# stepper.net
KiCad netlist of a schematic drawn in EAGLE
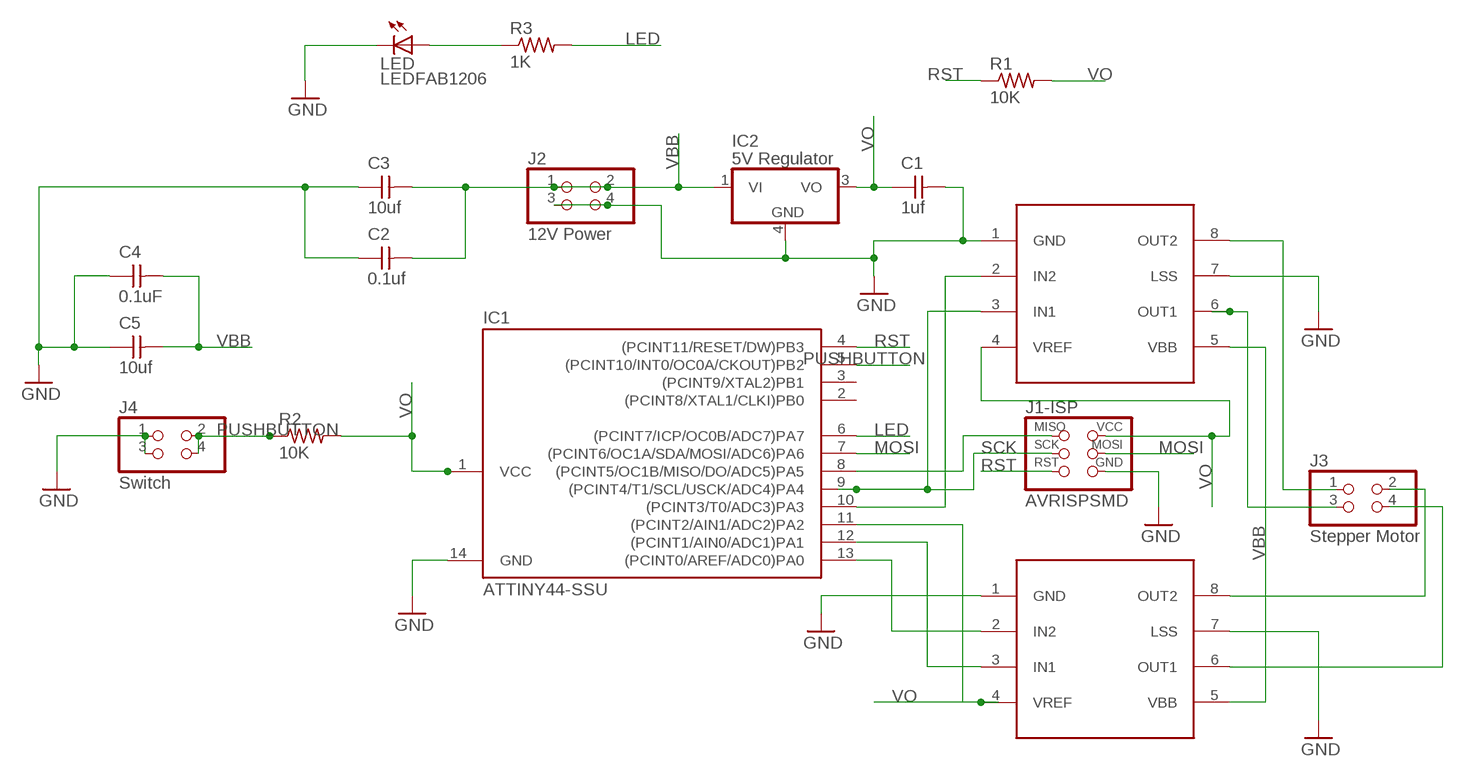
[diagram p0: schematic, sheet 1]

(export (version "E")
  (design (tool "Eeschema 10.0.6"))
  (components
    (comp (ref "C1")
      (value "1uf")
      (footprint "eagle-import:C1206FAB")
      (libsource (lib "eagle-import") (part "CAP-UNPOLARIZEDFAB"))
    )
    (comp (ref "C2")
      (value "0.1uf")
      (footprint "eagle-import:C1206FAB")
      (libsource (lib "eagle-import") (part "CAP-UNPOLARIZEDFAB"))
    )
    (comp (ref "C3")
      (value "10uf")
      (footprint "eagle-import:C1206FAB")
      (libsource (lib "eagle-import") (part "CAP-UNPOLARIZEDFAB"))
    )
    (comp (ref "C4")
      (value "0.1uF")
      (footprint "eagle-import:C1206FAB")
      (libsource (lib "eagle-import") (part "CAP-UNPOLARIZEDFAB"))
    )
    (comp (ref "C5")
      (value "10uf")
      (footprint "eagle-import:C1206FAB")
      (libsource (lib "eagle-import") (part "CAP-UNPOLARIZEDFAB"))
    )
    (comp (ref "IC1")
      (value "ATTINY44-SSU")
      (footprint "eagle-import:SOIC14")
      (libsource (lib "eagle-import") (part "ATTINY44-SSU"))
    )
    (comp (ref "IC2")
      (value "5V Regulator")
      (footprint "eagle-import:SOT223")
      (libsource (lib "eagle-import") (part "LM340?-MP05"))
    )
    (comp (ref "IC3")
      (value "A4950")
      (footprint "eagle-import:SOIC8")
      (libsource (lib "eagle-import") (part "A4953-H-BRIDGE-MOTOR-DRIVER"))
    )
    (comp (ref "IC4")
      (value "A4950")
      (footprint "eagle-import:SOIC8")
      (libsource (lib "eagle-import") (part "A4953-H-BRIDGE-MOTOR-DRIVER"))
    )
    (comp (ref "J1-ISP")
      (value "AVRISPSMD")
      (footprint "eagle-import:2X03SMD")
      (libsource (lib "eagle-import") (part "AVRISPSMD"))
    )
    (comp (ref "J2")
      (value "12V Power")
      (footprint "eagle-import:2X02SMD")
      (libsource (lib "eagle-import") (part "PINHD-2X2-SMD"))
    )
    (comp (ref "J3")
      (value "Stepper Motor")
      (footprint "eagle-import:2X02SMD")
      (libsource (lib "eagle-import") (part "PINHD-2X2-SMD"))
    )
    (comp (ref "J4")
      (value "Switch")
      (footprint "eagle-import:2X02SMD")
      (libsource (lib "eagle-import") (part "PINHD-2X2-SMD"))
    )
    (comp (ref "LED")
      (value "LEDFAB1206")
      (footprint "eagle-import:LED1206FAB")
      (libsource (lib "eagle-import") (part "LEDFAB1206"))
    )
    (comp (ref "R1")
      (value "10K")
      (footprint "eagle-import:R1206FAB")
      (libsource (lib "eagle-import") (part "RES-US1206FAB"))
    )
    (comp (ref "R2")
      (value "10K")
      (footprint "eagle-import:R1206FAB")
      (libsource (lib "eagle-import") (part "RES-US1206FAB"))
    )
    (comp (ref "R3")
      (value "1K")
      (footprint "eagle-import:R1206FAB")
      (libsource (lib "eagle-import") (part "RES-US1206FAB"))
    )
  )
  (nets
    (net (code "1") (name "/LED") (class "Default")
      (node (ref "IC1") (pin "6") (pinfunction "(PCINT7/ICP/OC0B/ADC7)PA7_6") (pintype "bidirectional"))
      (node (ref "R3") (pin "2") (pinfunction "2_2") (pintype "passive"))
    )
    (net (code "2") (name "/MOSI") (class "Default")
      (node (ref "IC1") (pin "7") (pinfunction "(PCINT6/OC1A/SDA/MOSI/ADC6)PA6_7") (pintype "bidirectional"))
      (node (ref "J1-ISP") (pin "4") (pinfunction "MOSI_4") (pintype "passive"))
    )
    (net (code "3") (name "/PUSHBUTTON") (class "Default")
      (node (ref "IC1") (pin "5") (pinfunction "(PCINT10/INT0/OC0A/CKOUT)PB2_5") (pintype "bidirectional"))
      (node (ref "J4") (pin "2") (pinfunction "2_2") (pintype "passive"))
      (node (ref "J4") (pin "4") (pinfunction "4_4") (pintype "passive"))
      (node (ref "R2") (pin "1") (pinfunction "1_1") (pintype "passive"))
    )
    (net (code "4") (name "/RST") (class "Default")
      (node (ref "IC1") (pin "4") (pinfunction "(PCINT11/RESET/DW)PB3_4") (pintype "bidirectional"))
      (node (ref "J1-ISP") (pin "5") (pinfunction "RST_5") (pintype "passive"))
      (node (ref "R1") (pin "1") (pinfunction "1_1") (pintype "passive"))
    )
    (net (code "5") (name "/SCK") (class "Default")
      (node (ref "IC1") (pin "9") (pinfunction "(PCINT4/T1/SCL/USCK/ADC4)PA4_9") (pintype "bidirectional"))
      (node (ref "IC4") (pin "3") (pinfunction "IN1_3") (pintype "bidirectional"))
      (node (ref "J1-ISP") (pin "3") (pinfunction "SCK_3") (pintype "passive"))
    )
    (net (code "6") (name "/VBB") (class "Default")
      (node (ref "C2") (pin "2") (pinfunction "2_2") (pintype "passive"))
      (node (ref "C3") (pin "2") (pinfunction "2_2") (pintype "passive"))
      (node (ref "C4") (pin "2") (pinfunction "2_2") (pintype "passive"))
      (node (ref "C5") (pin "2") (pinfunction "2_2") (pintype "passive"))
      (node (ref "IC2") (pin "1") (pinfunction "VI_1") (pintype "input"))
      (node (ref "IC3") (pin "5") (pinfunction "VBB_5") (pintype "bidirectional"))
      (node (ref "IC4") (pin "5") (pinfunction "VBB_5") (pintype "bidirectional"))
      (node (ref "J2") (pin "1") (pinfunction "1_1") (pintype "passive"))
      (node (ref "J2") (pin "2") (pinfunction "2_2") (pintype "passive"))
    )
    (net (code "7") (name "/VO") (class "Default")
      (node (ref "C1") (pin "1") (pinfunction "1_1") (pintype "passive"))
      (node (ref "IC1") (pin "1") (pinfunction "VCC_1") (pintype "power_in"))
      (node (ref "IC1") (pin "11") (pinfunction "(PCINT2/AIN1/ADC2)PA2_11") (pintype "bidirectional"))
      (node (ref "IC2") (pin "3") (pinfunction "VO_3") (pintype "passive"))
      (node (ref "IC3") (pin "4") (pinfunction "VREF_4") (pintype "bidirectional"))
      (node (ref "IC4") (pin "4") (pinfunction "VREF_4") (pintype "bidirectional"))
      (node (ref "J1-ISP") (pin "2") (pinfunction "VCC_2") (pintype "passive"))
      (node (ref "R1") (pin "2") (pinfunction "2_2") (pintype "passive"))
      (node (ref "R2") (pin "2") (pinfunction "2_2") (pintype "passive"))
    )
    (net (code "8") (name "GND") (class "Default")
      (node (ref "C1") (pin "2") (pinfunction "2_2") (pintype "passive"))
      (node (ref "C2") (pin "1") (pinfunction "1_1") (pintype "passive"))
      (node (ref "C3") (pin "1") (pinfunction "1_1") (pintype "passive"))
      (node (ref "C4") (pin "1") (pinfunction "1_1") (pintype "passive"))
      (node (ref "C5") (pin "1") (pinfunction "1_1") (pintype "passive"))
      (node (ref "IC1") (pin "14") (pinfunction "GND_14") (pintype "power_in"))
      (node (ref "IC2") (pin "4") (pinfunction "GND_4") (pintype "passive"))
      (node (ref "IC3") (pin "1") (pinfunction "GND_1") (pintype "bidirectional"))
      (node (ref "IC3") (pin "7") (pinfunction "LSS_7") (pintype "bidirectional"))
      (node (ref "IC4") (pin "1") (pinfunction "GND_1") (pintype "bidirectional"))
      (node (ref "IC4") (pin "7") (pinfunction "LSS_7") (pintype "bidirectional"))
      (node (ref "J1-ISP") (pin "6") (pinfunction "GND_6") (pintype "passive"))
      (node (ref "J2") (pin "3") (pinfunction "3_3") (pintype "passive"))
      (node (ref "J2") (pin "4") (pinfunction "4_4") (pintype "passive"))
      (node (ref "J4") (pin "1") (pinfunction "1_1") (pintype "passive"))
      (node (ref "J4") (pin "3") (pinfunction "3_3") (pintype "passive"))
      (node (ref "LED") (pin "2") (pinfunction "C_2") (pintype "passive"))
    )
    (net (code "9") (name "Net-(IC1-(PCINT0{slash}AREF{slash}ADC0)PA0)") (class "Default")
      (node (ref "IC1") (pin "13") (pinfunction "(PCINT0/AREF/ADC0)PA0_13") (pintype "bidirectional"))
      (node (ref "IC3") (pin "2") (pinfunction "IN2_2") (pintype "bidirectional"))
    )
    (net (code "10") (name "Net-(IC1-(PCINT1{slash}AIN0{slash}ADC1)PA1)") (class "Default")
      (node (ref "IC1") (pin "12") (pinfunction "(PCINT1/AIN0/ADC1)PA1_12") (pintype "bidirectional"))
      (node (ref "IC3") (pin "3") (pinfunction "IN1_3") (pintype "bidirectional"))
    )
    (net (code "11") (name "Net-(IC1-(PCINT3{slash}T0{slash}ADC3)PA3)") (class "Default")
      (node (ref "IC1") (pin "10") (pinfunction "(PCINT3/T0/ADC3)PA3_10") (pintype "bidirectional"))
      (node (ref "IC4") (pin "2") (pinfunction "IN2_2") (pintype "bidirectional"))
    )
    (net (code "12") (name "Net-(IC1-(PCINT5{slash}OC1B{slash}MISO{slash}DO{slash}ADC5)PA5)") (class "Default")
      (node (ref "IC1") (pin "8") (pinfunction "(PCINT5/OC1B/MISO/DO/ADC5)PA5_8") (pintype "bidirectional"))
      (node (ref "J1-ISP") (pin "1") (pinfunction "MISO_1") (pintype "passive"))
    )
    (net (code "13") (name "Net-(IC3-OUT1)") (class "Default")
      (node (ref "IC3") (pin "6") (pinfunction "OUT1_6") (pintype "bidirectional"))
      (node (ref "J3") (pin "4") (pinfunction "4_4") (pintype "passive"))
    )
    (net (code "14") (name "Net-(IC3-OUT2)") (class "Default")
      (node (ref "IC3") (pin "8") (pinfunction "OUT2_8") (pintype "bidirectional"))
      (node (ref "J3") (pin "2") (pinfunction "2_2") (pintype "passive"))
    )
    (net (code "15") (name "Net-(IC4-OUT1)") (class "Default")
      (node (ref "IC4") (pin "6") (pinfunction "OUT1_6") (pintype "bidirectional"))
      (node (ref "J3") (pin "3") (pinfunction "3_3") (pintype "passive"))
    )
    (net (code "16") (name "Net-(IC4-OUT2)") (class "Default")
      (node (ref "IC4") (pin "8") (pinfunction "OUT2_8") (pintype "bidirectional"))
      (node (ref "J3") (pin "1") (pinfunction "1_1") (pintype "passive"))
    )
    (net (code "17") (name "Net-(LED-A)") (class "Default")
      (node (ref "LED") (pin "1") (pinfunction "A_1") (pintype "passive"))
      (node (ref "R3") (pin "1") (pinfunction "1_1") (pintype "passive"))
    )
    (net (code "18") (name "unconnected-(IC1-(PCINT8{slash}XTAL1{slash}CLKI)PB0-Pad2)") (class "Default")
      (node (ref "IC1") (pin "2") (pinfunction "(PCINT8/XTAL1/CLKI)PB0_2") (pintype "bidirectional"))
    )
    (net (code "19") (name "unconnected-(IC1-(PCINT9{slash}XTAL2)PB1-Pad3)") (class "Default")
      (node (ref "IC1") (pin "3") (pinfunction "(PCINT9/XTAL2)PB1_3") (pintype "bidirectional"))
    )
  )
)
